# 6502Attempt1.net
KiCad netlist of a schematic drawn in EasyEDA
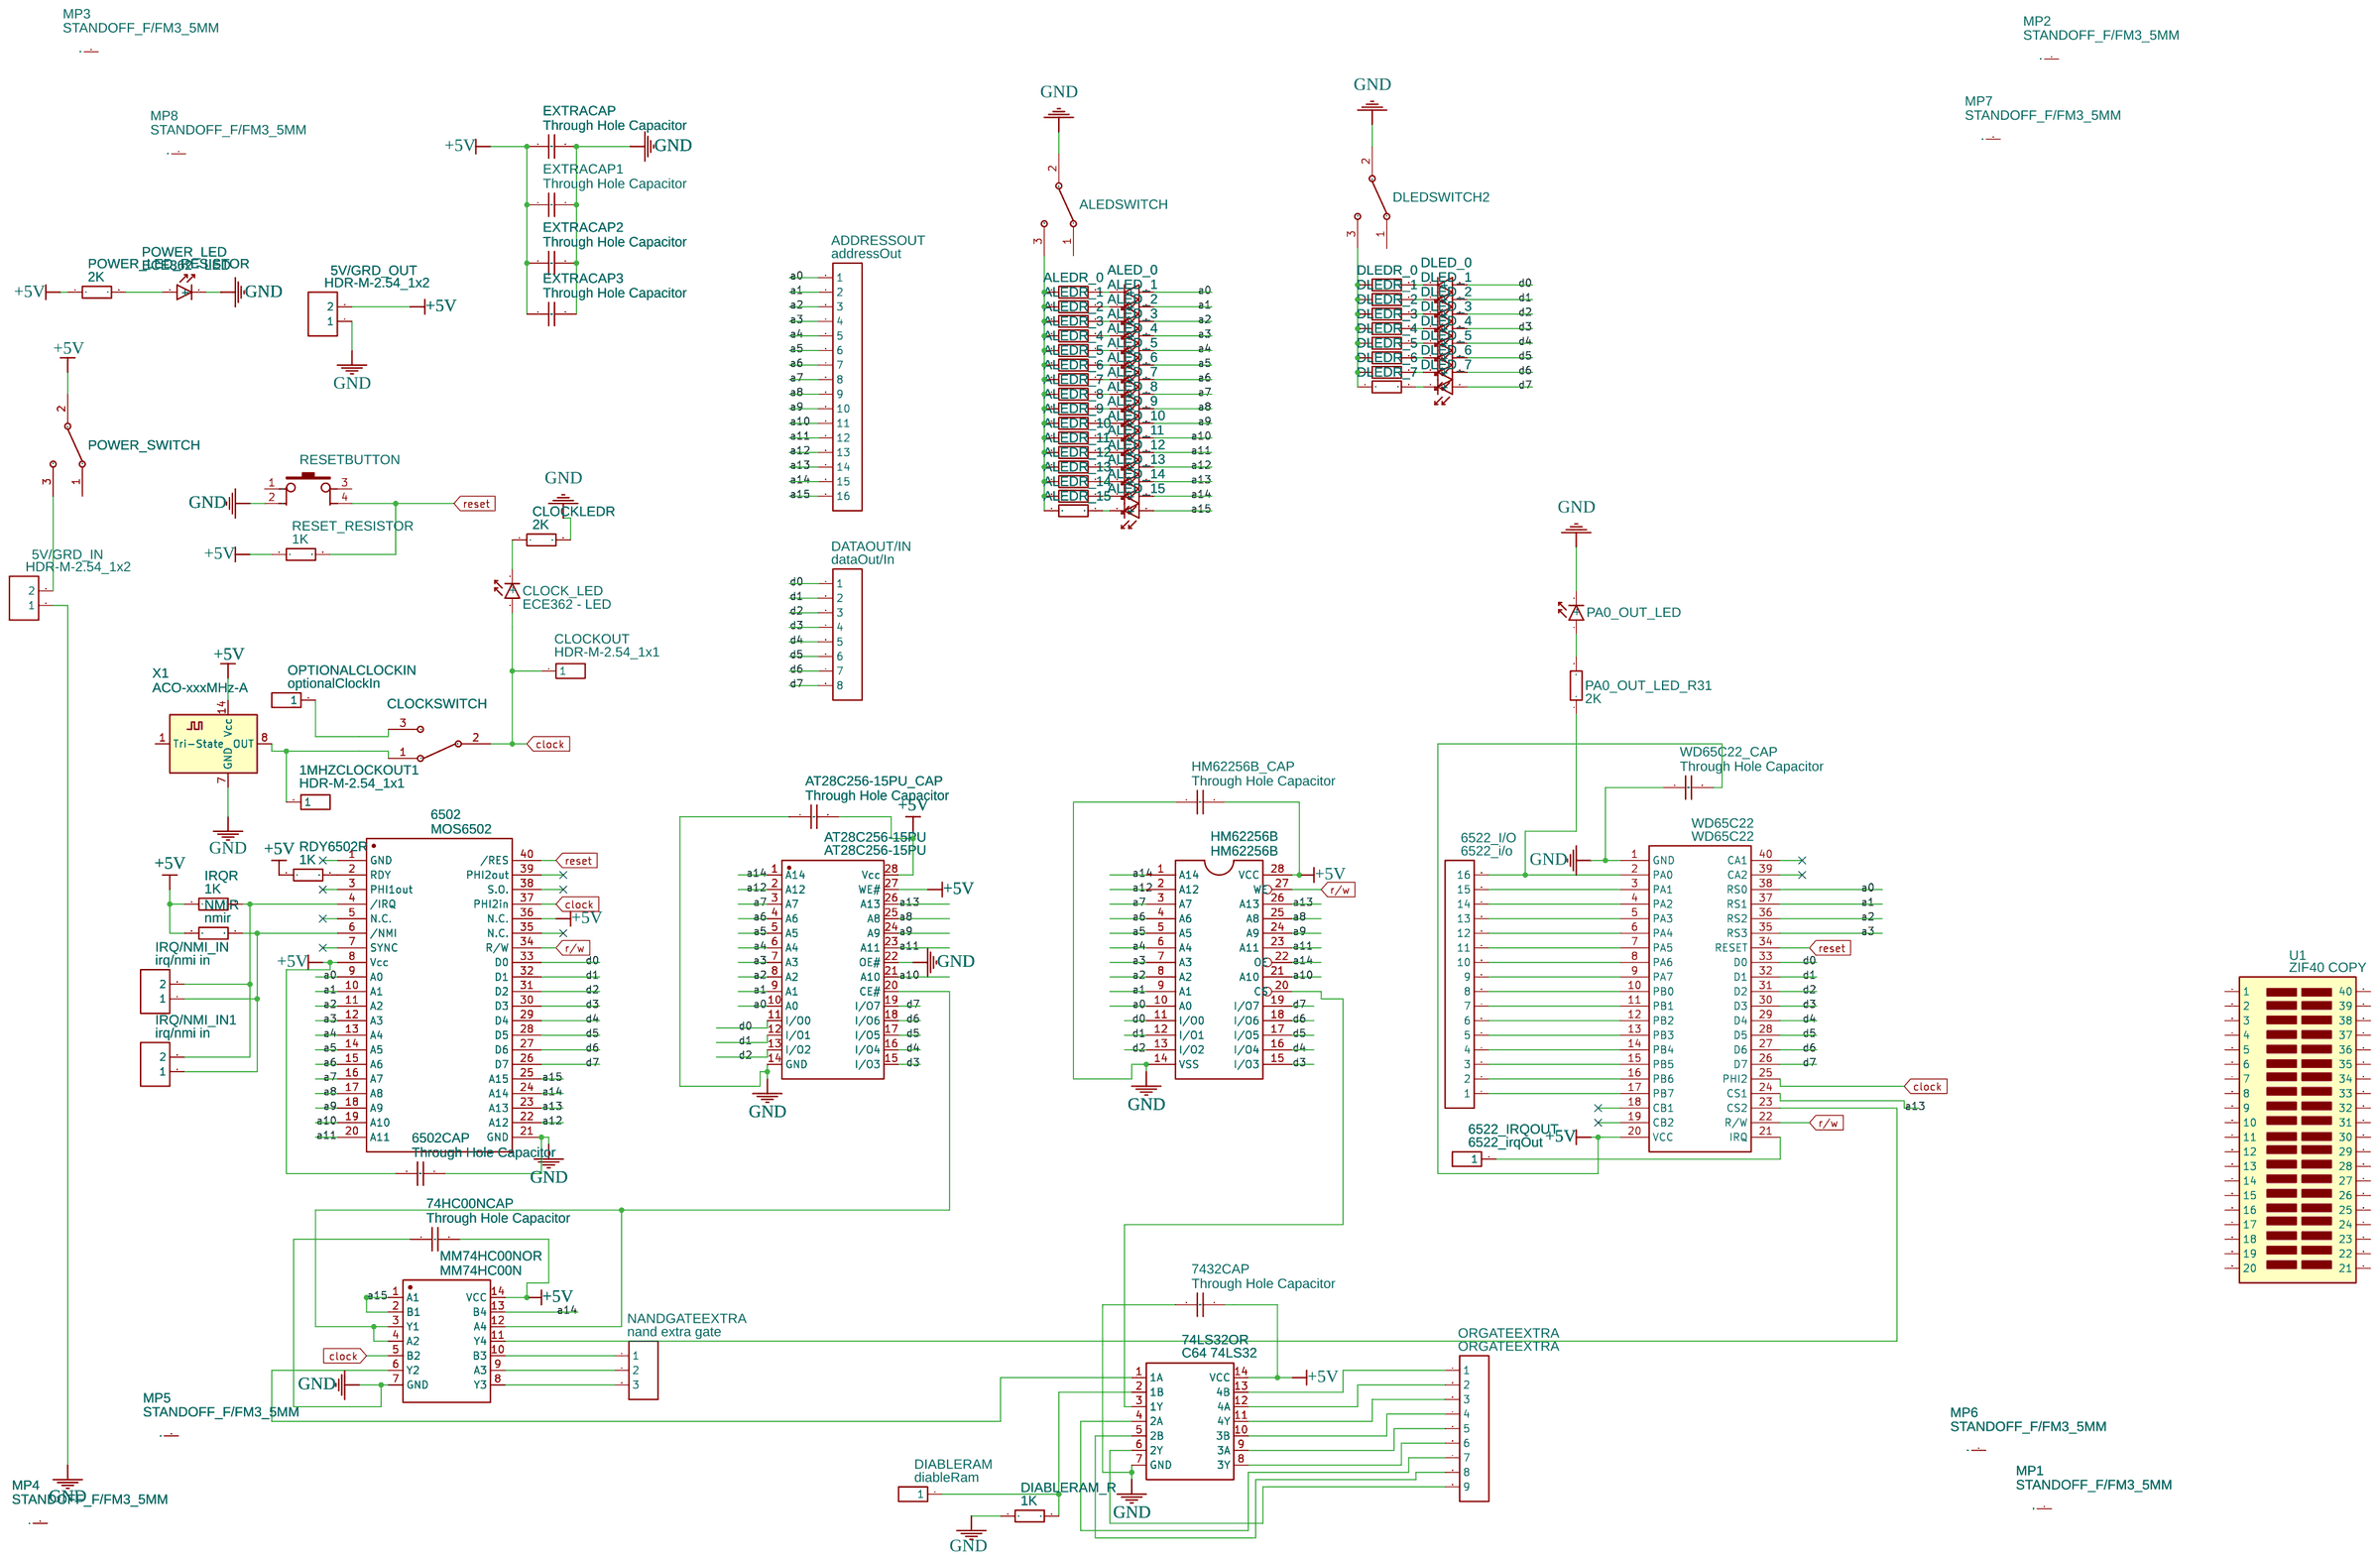
[diagram p0: schematic sheet]

(export (version "E")
  (design (tool "Eeschema 10.0.6"))
  (components
    (comp (ref "1MHZCLOCKOUT1")
      (value "HDR-M-2.54_1x1")
      (fields (field (name "BOM_Supplier Part") "C81276"))
      (libsource (lib "") (part "HDR-M-2.54_1x1"))
    )
    (comp (ref "5V/GRD_IN")
      (value "HDR-M-2.54_1x2")
      (fields (field (name "BOM_Supplier Part") "C124375"))
      (libsource (lib "") (part "HDR-M-2.54_1x2_1"))
    )
    (comp (ref "5V/GRD_OUT")
      (value "HDR-M-2.54_1x2")
      (fields (field (name "BOM_Supplier Part") "C124375"))
      (libsource (lib "") (part "HDR-M-2.54_1x2"))
    )
    (comp (ref "74HC00NCAP")
      (value "Through Hole Capacitor")
      (fields (field (name "BOM_Manufacturer Part") "TAP106K016SCS"))
      (libsource (lib "") (part "Through Hole Capacitor_1"))
    )
    (comp (ref "74LS32OR") (value "C64 74LS32") (libsource (lib "") (part "C64 74LS32")))
    (comp (ref "6502") (value "MOS6502") (libsource (lib "") (part "MOS6502")))
    (comp (ref "6502CAP")
      (value "Through Hole Capacitor")
      (fields (field (name "BOM_Manufacturer Part") "TAP106K016SCS"))
      (libsource (lib "") (part "Through Hole Capacitor_2"))
    )
    (comp (ref "6522_I/O") (value "6522_i/o") (libsource (lib "") (part "HDR-M-2.54_1x16_1")))
    (comp (ref "6522_IRQOUT")
      (value "6522_irqOut")
      (fields (field (name "BOM_Supplier Part") "C81276"))
      (libsource (lib "") (part "HDR-M-2.54_1x1_3"))
    )
    (comp (ref "7432CAP")
      (value "Through Hole Capacitor")
      (fields (field (name "BOM_Manufacturer Part") "TAP106K016SCS"))
      (libsource (lib "") (part "Through Hole Capacitor_3"))
    )
    (comp (ref "ADDRESSOUT") (value "addressOut") (libsource (lib "") (part "HDR-M-2.54_1x16")))
    (comp (ref "ALEDR_0")
      (value "2K")
      (fields
        (field (name "BOM_Manufacturer Part") "EWWR0006J10K0T9")
        (field (name "BOM_Supplier Part") "C348946")
      )
      (libsource (lib "") (part "GENERIC THROUGH HOLE RESISTOR 2"))
    )
    (comp (ref "ALEDR_1")
      (value "2K")
      (fields
        (field (name "BOM_Manufacturer Part") "EWWR0006J10K0T9")
        (field (name "BOM_Supplier Part") "C348946")
      )
      (libsource (lib "") (part "GENERIC THROUGH HOLE RESISTOR 2"))
    )
    (comp (ref "ALEDR_2")
      (value "2K")
      (fields
        (field (name "BOM_Manufacturer Part") "EWWR0006J10K0T9")
        (field (name "BOM_Supplier Part") "C348946")
      )
      (libsource (lib "") (part "GENERIC THROUGH HOLE RESISTOR 2"))
    )
    (comp (ref "ALEDR_3")
      (value "2K")
      (fields
        (field (name "BOM_Manufacturer Part") "EWWR0006J10K0T9")
        (field (name "BOM_Supplier Part") "C348946")
      )
      (libsource (lib "") (part "GENERIC THROUGH HOLE RESISTOR 2"))
    )
    (comp (ref "ALEDR_4")
      (value "2K")
      (fields
        (field (name "BOM_Manufacturer Part") "EWWR0006J10K0T9")
        (field (name "BOM_Supplier Part") "C348946")
      )
      (libsource (lib "") (part "GENERIC THROUGH HOLE RESISTOR 2"))
    )
    (comp (ref "ALEDR_5")
      (value "2K")
      (fields
        (field (name "BOM_Manufacturer Part") "EWWR0006J10K0T9")
        (field (name "BOM_Supplier Part") "C348946")
      )
      (libsource (lib "") (part "GENERIC THROUGH HOLE RESISTOR 2"))
    )
    (comp (ref "ALEDR_6")
      (value "2K")
      (fields
        (field (name "BOM_Manufacturer Part") "EWWR0006J10K0T9")
        (field (name "BOM_Supplier Part") "C348946")
      )
      (libsource (lib "") (part "GENERIC THROUGH HOLE RESISTOR 2"))
    )
    (comp (ref "ALEDR_7")
      (value "2K")
      (fields
        (field (name "BOM_Manufacturer Part") "EWWR0006J10K0T9")
        (field (name "BOM_Supplier Part") "C348946")
      )
      (libsource (lib "") (part "GENERIC THROUGH HOLE RESISTOR 2"))
    )
    (comp (ref "ALEDR_8")
      (value "2K")
      (fields
        (field (name "BOM_Manufacturer Part") "EWWR0006J10K0T9")
        (field (name "BOM_Supplier Part") "C348946")
      )
      (libsource (lib "") (part "GENERIC THROUGH HOLE RESISTOR 2"))
    )
    (comp (ref "ALEDR_9")
      (value "2K")
      (fields
        (field (name "BOM_Manufacturer Part") "EWWR0006J10K0T9")
        (field (name "BOM_Supplier Part") "C348946")
      )
      (libsource (lib "") (part "GENERIC THROUGH HOLE RESISTOR 2"))
    )
    (comp (ref "ALEDR_10")
      (value "2K")
      (fields
        (field (name "BOM_Manufacturer Part") "EWWR0006J10K0T9")
        (field (name "BOM_Supplier Part") "C348946")
      )
      (libsource (lib "") (part "GENERIC THROUGH HOLE RESISTOR 2"))
    )
    (comp (ref "ALEDR_11")
      (value "2K")
      (fields
        (field (name "BOM_Manufacturer Part") "EWWR0006J10K0T9")
        (field (name "BOM_Supplier Part") "C348946")
      )
      (libsource (lib "") (part "GENERIC THROUGH HOLE RESISTOR 2"))
    )
    (comp (ref "ALEDR_12")
      (value "2K")
      (fields
        (field (name "BOM_Manufacturer Part") "EWWR0006J10K0T9")
        (field (name "BOM_Supplier Part") "C348946")
      )
      (libsource (lib "") (part "GENERIC THROUGH HOLE RESISTOR 2"))
    )
    (comp (ref "ALEDR_13")
      (value "2K")
      (fields
        (field (name "BOM_Manufacturer Part") "EWWR0006J10K0T9")
        (field (name "BOM_Supplier Part") "C348946")
      )
      (libsource (lib "") (part "GENERIC THROUGH HOLE RESISTOR 2"))
    )
    (comp (ref "ALEDR_14")
      (value "2K")
      (fields
        (field (name "BOM_Manufacturer Part") "EWWR0006J10K0T9")
        (field (name "BOM_Supplier Part") "C348946")
      )
      (libsource (lib "") (part "GENERIC THROUGH HOLE RESISTOR 2"))
    )
    (comp (ref "ALEDR_15")
      (value "2K")
      (fields
        (field (name "BOM_Manufacturer Part") "EWWR0006J10K0T9")
        (field (name "BOM_Supplier Part") "C348946")
      )
      (libsource (lib "") (part "GENERIC THROUGH HOLE RESISTOR 2"))
    )
    (comp (ref "ALEDSWITCH")
      (value "Slide Switches_SPDT(Single Pole Double Throw)")
      (libsource (lib "") (part "Slide Switches_SPDT(Single Pole Double Throw)_1"))
    )
    (comp (ref "ALED_0") (value "ECE362 - LED") (libsource (lib "") (part "ECE362 - LED")))
    (comp (ref "ALED_1") (value "ECE362 - LED") (libsource (lib "") (part "ECE362 - LED")))
    (comp (ref "ALED_2") (value "ECE362 - LED") (libsource (lib "") (part "ECE362 - LED")))
    (comp (ref "ALED_3") (value "ECE362 - LED") (libsource (lib "") (part "ECE362 - LED")))
    (comp (ref "ALED_4") (value "ECE362 - LED") (libsource (lib "") (part "ECE362 - LED")))
    (comp (ref "ALED_5") (value "ECE362 - LED") (libsource (lib "") (part "ECE362 - LED")))
    (comp (ref "ALED_6") (value "ECE362 - LED") (libsource (lib "") (part "ECE362 - LED")))
    (comp (ref "ALED_7") (value "ECE362 - LED") (libsource (lib "") (part "ECE362 - LED")))
    (comp (ref "ALED_8") (value "ECE362 - LED") (libsource (lib "") (part "ECE362 - LED")))
    (comp (ref "ALED_9") (value "ECE362 - LED") (libsource (lib "") (part "ECE362 - LED")))
    (comp (ref "ALED_10") (value "ECE362 - LED") (libsource (lib "") (part "ECE362 - LED")))
    (comp (ref "ALED_11") (value "ECE362 - LED") (libsource (lib "") (part "ECE362 - LED")))
    (comp (ref "ALED_12") (value "ECE362 - LED") (libsource (lib "") (part "ECE362 - LED")))
    (comp (ref "ALED_13") (value "ECE362 - LED") (libsource (lib "") (part "ECE362 - LED")))
    (comp (ref "ALED_14") (value "ECE362 - LED") (libsource (lib "") (part "ECE362 - LED")))
    (comp (ref "ALED_15") (value "ECE362 - LED") (libsource (lib "") (part "ECE362 - LED")))
    (comp (ref "AT28C256-15PU")
      (value "AT28C256-15PU")
      (fields (field (name "BOM_Supplier Part") "C1348752"))
      (libsource (lib "") (part "AT28C256-15PU"))
    )
    (comp (ref "AT28C256-15PU_CAP")
      (value "Through Hole Capacitor")
      (fields (field (name "BOM_Manufacturer Part") "TAP106K016SCS"))
      (libsource (lib "") (part "Through Hole Capacitor_6"))
    )
    (comp (ref "CLOCKLEDR")
      (value "2K")
      (fields
        (field (name "BOM_Manufacturer Part") "EWWR0006J10K0T9")
        (field (name "BOM_Supplier Part") "C348946")
      )
      (libsource (lib "") (part "GENERIC THROUGH HOLE RESISTOR 2_1"))
    )
    (comp (ref "CLOCKOUT")
      (value "HDR-M-2.54_1x1")
      (fields (field (name "BOM_Supplier Part") "C81276"))
      (libsource (lib "") (part "HDR-M-2.54_1x1_1"))
    )
    (comp (ref "CLOCKSWITCH")
      (value "Slide Switches_SPDT(Single Pole Double Throw)")
      (libsource (lib "") (part "Slide Switches_SPDT(Single Pole Double Throw)_3"))
    )
    (comp (ref "CLOCK_LED") (value "ECE362 - LED") (libsource (lib "") (part "ECE362 - LED_3")))
    (comp (ref "DATAOUT/IN")
      (value "dataOut/In")
      (fields (field (name "BOM_Supplier Part") "C190820"))
      (libsource (lib "") (part "HDR-M-2.54_1x8"))
    )
    (comp (ref "DIABLERAM")
      (value "diableRam")
      (fields (field (name "BOM_Supplier Part") "C81276"))
      (libsource (lib "") (part "HDR-M-2.54_1x1_2"))
    )
    (comp (ref "DIABLERAM_R")
      (value "1K")
      (fields
        (field (name "BOM_Manufacturer Part") "EWWR0006J10K0T9")
        (field (name "BOM_Supplier Part") "C348946")
      )
      (libsource (lib "") (part "GENERIC THROUGH HOLE RESISTOR 2_6"))
    )
    (comp (ref "DLEDR_0")
      (value "2K")
      (fields
        (field (name "BOM_Manufacturer Part") "EWWR0006J10K0T9")
        (field (name "BOM_Supplier Part") "C348946")
      )
      (libsource (lib "") (part "GENERIC THROUGH HOLE RESISTOR 2_2"))
    )
    (comp (ref "DLEDR_1")
      (value "2K")
      (fields
        (field (name "BOM_Manufacturer Part") "EWWR0006J10K0T9")
        (field (name "BOM_Supplier Part") "C348946")
      )
      (libsource (lib "") (part "GENERIC THROUGH HOLE RESISTOR 2_2"))
    )
    (comp (ref "DLEDR_2")
      (value "2K")
      (fields
        (field (name "BOM_Manufacturer Part") "EWWR0006J10K0T9")
        (field (name "BOM_Supplier Part") "C348946")
      )
      (libsource (lib "") (part "GENERIC THROUGH HOLE RESISTOR 2_2"))
    )
    (comp (ref "DLEDR_3")
      (value "2K")
      (fields
        (field (name "BOM_Manufacturer Part") "EWWR0006J10K0T9")
        (field (name "BOM_Supplier Part") "C348946")
      )
      (libsource (lib "") (part "GENERIC THROUGH HOLE RESISTOR 2_2"))
    )
    (comp (ref "DLEDR_4")
      (value "2K")
      (fields
        (field (name "BOM_Manufacturer Part") "EWWR0006J10K0T9")
        (field (name "BOM_Supplier Part") "C348946")
      )
      (libsource (lib "") (part "GENERIC THROUGH HOLE RESISTOR 2_2"))
    )
    (comp (ref "DLEDR_5")
      (value "2K")
      (fields
        (field (name "BOM_Manufacturer Part") "EWWR0006J10K0T9")
        (field (name "BOM_Supplier Part") "C348946")
      )
      (libsource (lib "") (part "GENERIC THROUGH HOLE RESISTOR 2_2"))
    )
    (comp (ref "DLEDR_6")
      (value "2K")
      (fields
        (field (name "BOM_Manufacturer Part") "EWWR0006J10K0T9")
        (field (name "BOM_Supplier Part") "C348946")
      )
      (libsource (lib "") (part "GENERIC THROUGH HOLE RESISTOR 2_2"))
    )
    (comp (ref "DLEDR_7")
      (value "2K")
      (fields
        (field (name "BOM_Manufacturer Part") "EWWR0006J10K0T9")
        (field (name "BOM_Supplier Part") "C348946")
      )
      (libsource (lib "") (part "GENERIC THROUGH HOLE RESISTOR 2_2"))
    )
    (comp (ref "DLEDSWITCH2")
      (value "Slide Switches_SPDT(Single Pole Double Throw)")
      (libsource (lib "") (part "Slide Switches_SPDT(Single Pole Double Throw)"))
    )
    (comp (ref "DLED_0") (value "ECE362 - LED") (libsource (lib "") (part "ECE362 - LED_1")))
    (comp (ref "DLED_1") (value "ECE362 - LED") (libsource (lib "") (part "ECE362 - LED_1")))
    (comp (ref "DLED_2") (value "ECE362 - LED") (libsource (lib "") (part "ECE362 - LED_1")))
    (comp (ref "DLED_3") (value "ECE362 - LED") (libsource (lib "") (part "ECE362 - LED_1")))
    (comp (ref "DLED_4") (value "ECE362 - LED") (libsource (lib "") (part "ECE362 - LED_1")))
    (comp (ref "DLED_5") (value "ECE362 - LED") (libsource (lib "") (part "ECE362 - LED_1")))
    (comp (ref "DLED_6") (value "ECE362 - LED") (libsource (lib "") (part "ECE362 - LED_1")))
    (comp (ref "DLED_7") (value "ECE362 - LED") (libsource (lib "") (part "ECE362 - LED_1")))
    (comp (ref "EXTRACAP")
      (value "Through Hole Capacitor")
      (fields (field (name "BOM_Manufacturer Part") "TAP106K016SCS"))
      (libsource (lib "") (part "Through Hole Capacitor"))
    )
    (comp (ref "EXTRACAP1")
      (value "Through Hole Capacitor")
      (fields (field (name "BOM_Manufacturer Part") "TAP106K016SCS"))
      (libsource (lib "") (part "Through Hole Capacitor"))
    )
    (comp (ref "EXTRACAP2")
      (value "Through Hole Capacitor")
      (fields (field (name "BOM_Manufacturer Part") "TAP106K016SCS"))
      (libsource (lib "") (part "Through Hole Capacitor"))
    )
    (comp (ref "EXTRACAP3")
      (value "Through Hole Capacitor")
      (fields (field (name "BOM_Manufacturer Part") "TAP106K016SCS"))
      (libsource (lib "") (part "Through Hole Capacitor"))
    )
    (comp (ref "HM62256B") (value "HM62256B") (libsource (lib "") (part "HM62256B")))
    (comp (ref "HM62256B_CAP")
      (value "Through Hole Capacitor")
      (fields (field (name "BOM_Manufacturer Part") "TAP106K016SCS"))
      (libsource (lib "") (part "Through Hole Capacitor_5"))
    )
    (comp (ref "IRQ/NMI_IN")
      (value "irq/nmi in")
      (fields (field (name "BOM_Supplier Part") "C49661"))
      (libsource (lib "") (part "HDR-F-2.54_1x2"))
    )
    (comp (ref "IRQ/NMI_IN1")
      (value "irq/nmi in")
      (fields (field (name "BOM_Supplier Part") "C49661"))
      (libsource (lib "") (part "HDR-F-2.54_1x2"))
    )
    (comp (ref "IRQR")
      (value "1K")
      (fields
        (field (name "BOM_Manufacturer Part") "EWWR0006J10K0T9")
        (field (name "BOM_Supplier Part") "C348946")
      )
      (libsource (lib "") (part "GENERIC THROUGH HOLE RESISTOR 2_7"))
    )
    (comp (ref "MM74HC00NOR") (value "MM74HC00N") (libsource (lib "") (part "MM74HC00N")))
    (comp (ref "MP1") (value "STANDOFF_F/FM3_5MM") (libsource (lib "") (part "STANDOFF_F/FM3_5MM")))
    (comp (ref "MP2") (value "STANDOFF_F/FM3_5MM") (libsource (lib "") (part "STANDOFF_F/FM3_5MM")))
    (comp (ref "MP3") (value "STANDOFF_F/FM3_5MM") (libsource (lib "") (part "STANDOFF_F/FM3_5MM")))
    (comp (ref "MP4") (value "STANDOFF_F/FM3_5MM") (libsource (lib "") (part "STANDOFF_F/FM3_5MM")))
    (comp (ref "MP5") (value "STANDOFF_F/FM3_5MM") (libsource (lib "") (part "STANDOFF_F/FM3_5MM")))
    (comp (ref "MP6") (value "STANDOFF_F/FM3_5MM") (libsource (lib "") (part "STANDOFF_F/FM3_5MM")))
    (comp (ref "MP7") (value "STANDOFF_F/FM3_5MM") (libsource (lib "") (part "STANDOFF_F/FM3_5MM")))
    (comp (ref "MP8") (value "STANDOFF_F/FM3_5MM") (libsource (lib "") (part "STANDOFF_F/FM3_5MM")))
    (comp (ref "NANDGATEEXTRA")
      (value "nand extra gate")
      (fields (field (name "BOM_Supplier Part") "C180248"))
      (libsource (lib "") (part "HDR-M-2.54_1x3"))
    )
    (comp (ref "NMIR")
      (value "nmir")
      (fields
        (field (name "BOM_Manufacturer Part") "EWWR0006J10K0T9")
        (field (name "BOM_Supplier Part") "C348946")
      )
      (libsource (lib "") (part "GENERIC THROUGH HOLE RESISTOR 2_3"))
    )
    (comp (ref "OPTIONALCLOCKIN")
      (value "optionalClockIn")
      (fields (field (name "BOM_Supplier Part") "C81276"))
      (libsource (lib "") (part "HDR-M-2.54_1x1_4"))
    )
    (comp (ref "ORGATEEXTRA")
      (value "ORGATEEXTRA")
      (fields (field (name "BOM_Supplier Part") "C225484"))
      (libsource (lib "") (part "HDR-M-2.54_1x9"))
    )
    (comp (ref "PA0_OUT_LED") (value "ECE362 - LED") (libsource (lib "") (part "ECE362 - LED_4")))
    (comp (ref "PA0_OUT_LED_R31")
      (value "2K")
      (fields
        (field (name "BOM_Manufacturer Part") "EWWR0006J10K0T9")
        (field (name "BOM_Supplier Part") "C348946")
      )
      (libsource (lib "") (part "GENERIC THROUGH HOLE RESISTOR 2_5"))
    )
    (comp (ref "POWER_LED") (value "ECE362 - LED") (libsource (lib "") (part "ECE362 - LED_2")))
    (comp (ref "POWER_LED_RESISTOR")
      (value "2K")
      (fields
        (field (name "BOM_Manufacturer Part") "EWWR0006J10K0T9")
        (field (name "BOM_Supplier Part") "C348946")
      )
      (libsource (lib "") (part "GENERIC THROUGH HOLE RESISTOR 2_8"))
    )
    (comp (ref "POWER_SWITCH")
      (value "Slide Switches_SPDT(Single Pole Double Throw)")
      (libsource (lib "") (part "Slide Switches_SPDT(Single Pole Double Throw)_2"))
    )
    (comp (ref "RDY6502R")
      (value "1K")
      (fields
        (field (name "BOM_Manufacturer Part") "EWWR0006J10K0T9")
        (field (name "BOM_Supplier Part") "C348946")
      )
      (libsource (lib "") (part "GENERIC THROUGH HOLE RESISTOR 2_4"))
    )
    (comp (ref "RESETBUTTON")
      (value "PUSHBUTTON 4PIN (4.5MM*6.1MM) COPY")
      (libsource (lib "") (part "PUSHBUTTON 4PIN (4.5MM*6.1MM) COPY"))
    )
    (comp (ref "RESET_RESISTOR")
      (value "1K")
      (fields
        (field (name "BOM_Manufacturer Part") "EWWR0006J10K0T9")
        (field (name "BOM_Supplier Part") "C348946")
      )
      (libsource (lib "") (part "GENERIC THROUGH HOLE RESISTOR 2_9"))
    )
    (comp (ref "U1")
      (value "ZIF40 COPY")
      (fields (field (name "BOM_Manufacturer Part") "New SchematicLib"))
      (libsource (lib "") (part "ZIF40 COPY"))
    )
    (comp (ref "WD65C22") (value "WD65C22") (libsource (lib "") (part "WD65C22")))
    (comp (ref "WD65C22_CAP")
      (value "Through Hole Capacitor")
      (fields (field (name "BOM_Manufacturer Part") "TAP106K016SCS"))
      (libsource (lib "") (part "Through Hole Capacitor_4"))
    )
    (comp (ref "X1") (value "ACO-xxxMHz-A") (libsource (lib "") (part "ACO-xxxMHz-A")))
  )
  (nets
    (net (code "1") (name "+5V") (class "Default")
      (node (ref "5V/GRD_OUT") (pin "2") (pinfunction "2_2") (pintype "unspecified"))
      (node (ref "6502") (pin "36") (pinfunction "N.C._36") (pintype "unspecified"))
      (node (ref "6502") (pin "8") (pinfunction "Vcc_8") (pintype "unspecified"))
      (node (ref "6502CAP") (pin "1") (pinfunction "1_1") (pintype "unspecified"))
      (node (ref "7432CAP") (pin "2") (pinfunction "2_2") (pintype "unspecified"))
      (node (ref "74HC00NCAP") (pin "2") (pinfunction "2_2") (pintype "unspecified"))
      (node (ref "74LS32OR") (pin "14") (pinfunction "VCC_14") (pintype "unspecified"))
      (node (ref "AT28C256-15PU") (pin "27") (pinfunction "WE#_27") (pintype "unspecified"))
      (node (ref "AT28C256-15PU") (pin "28") (pinfunction "Vcc_28") (pintype "unspecified"))
      (node (ref "AT28C256-15PU_CAP") (pin "2") (pinfunction "2_2") (pintype "unspecified"))
      (node (ref "EXTRACAP") (pin "1") (pinfunction "1_1") (pintype "unspecified"))
      (node (ref "EXTRACAP1") (pin "1") (pinfunction "1_1") (pintype "unspecified"))
      (node (ref "EXTRACAP2") (pin "1") (pinfunction "1_1") (pintype "unspecified"))
      (node (ref "EXTRACAP3") (pin "1") (pinfunction "1_1") (pintype "unspecified"))
      (node (ref "HM62256B") (pin "28") (pinfunction "VCC_28") (pintype "unspecified"))
      (node (ref "HM62256B_CAP") (pin "2") (pinfunction "2_2") (pintype "unspecified"))
      (node (ref "IRQR") (pin "1") (pinfunction "1_1") (pintype "unspecified"))
      (node (ref "MM74HC00NOR") (pin "14") (pinfunction "VCC_14") (pintype "unspecified"))
      (node (ref "NMIR") (pin "1") (pinfunction "1_1") (pintype "unspecified"))
      (node (ref "POWER_LED_RESISTOR") (pin "1") (pinfunction "1_1") (pintype "unspecified"))
      (node (ref "POWER_SWITCH") (pin "2") (pinfunction "2_2") (pintype "unspecified"))
      (node (ref "RDY6502R") (pin "1") (pinfunction "1_1") (pintype "unspecified"))
      (node (ref "RESET_RESISTOR") (pin "1") (pinfunction "1_1") (pintype "unspecified"))
      (node (ref "WD65C22") (pin "20") (pinfunction "VCC_20") (pintype "unspecified"))
      (node (ref "WD65C22_CAP") (pin "2") (pinfunction "2_2") (pintype "unspecified"))
      (node (ref "X1") (pin "14") (pinfunction "Vcc_14") (pintype "bidirectional"))
    )
    (net (code "2") (name "/a0") (class "Default")
      (node (ref "6502") (pin "9") (pinfunction "A0_9") (pintype "unspecified"))
      (node (ref "ADDRESSOUT") (pin "1") (pinfunction "1_1") (pintype "unspecified"))
      (node (ref "ALED_0") (pin "1") (pinfunction "+_1") (pintype "unspecified"))
      (node (ref "AT28C256-15PU") (pin "10") (pinfunction "A0_10") (pintype "unspecified"))
      (node (ref "HM62256B") (pin "10") (pinfunction "A0_10") (pintype "unspecified"))
      (node (ref "WD65C22") (pin "38") (pinfunction "RS0_38") (pintype "unspecified"))
    )
    (net (code "3") (name "/a1") (class "Default")
      (node (ref "6502") (pin "10") (pinfunction "A1_10") (pintype "unspecified"))
      (node (ref "ADDRESSOUT") (pin "2") (pinfunction "2_2") (pintype "unspecified"))
      (node (ref "ALED_1") (pin "1") (pinfunction "+_1") (pintype "unspecified"))
      (node (ref "AT28C256-15PU") (pin "9") (pinfunction "A1_9") (pintype "unspecified"))
      (node (ref "HM62256B") (pin "9") (pinfunction "A1_9") (pintype "unspecified"))
      (node (ref "WD65C22") (pin "37") (pinfunction "RS1_37") (pintype "unspecified"))
    )
    (net (code "4") (name "/a2") (class "Default")
      (node (ref "6502") (pin "11") (pinfunction "A2_11") (pintype "unspecified"))
      (node (ref "ADDRESSOUT") (pin "3") (pinfunction "3_3") (pintype "unspecified"))
      (node (ref "ALED_2") (pin "1") (pinfunction "+_1") (pintype "unspecified"))
      (node (ref "AT28C256-15PU") (pin "8") (pinfunction "A2_8") (pintype "unspecified"))
      (node (ref "HM62256B") (pin "8") (pinfunction "A2_8") (pintype "unspecified"))
      (node (ref "WD65C22") (pin "36") (pinfunction "RS2_36") (pintype "unspecified"))
    )
    (net (code "5") (name "/a3") (class "Default")
      (node (ref "6502") (pin "12") (pinfunction "A3_12") (pintype "unspecified"))
      (node (ref "ADDRESSOUT") (pin "4") (pinfunction "4_4") (pintype "unspecified"))
      (node (ref "ALED_3") (pin "1") (pinfunction "+_1") (pintype "unspecified"))
      (node (ref "AT28C256-15PU") (pin "7") (pinfunction "A3_7") (pintype "unspecified"))
      (node (ref "HM62256B") (pin "7") (pinfunction "A3_7") (pintype "unspecified"))
      (node (ref "WD65C22") (pin "35") (pinfunction "RS3_35") (pintype "unspecified"))
    )
    (net (code "6") (name "/a4") (class "Default")
      (node (ref "6502") (pin "13") (pinfunction "A4_13") (pintype "unspecified"))
      (node (ref "ADDRESSOUT") (pin "5") (pinfunction "5_5") (pintype "unspecified"))
      (node (ref "ALED_4") (pin "1") (pinfunction "+_1") (pintype "unspecified"))
      (node (ref "AT28C256-15PU") (pin "6") (pinfunction "A4_6") (pintype "unspecified"))
      (node (ref "HM62256B") (pin "6") (pinfunction "A4_6") (pintype "unspecified"))
    )
    (net (code "7") (name "/a5") (class "Default")
      (node (ref "6502") (pin "14") (pinfunction "A5_14") (pintype "unspecified"))
      (node (ref "ADDRESSOUT") (pin "6") (pinfunction "6_6") (pintype "unspecified"))
      (node (ref "ALED_5") (pin "1") (pinfunction "+_1") (pintype "unspecified"))
      (node (ref "AT28C256-15PU") (pin "5") (pinfunction "A5_5") (pintype "unspecified"))
      (node (ref "HM62256B") (pin "5") (pinfunction "A5_5") (pintype "unspecified"))
    )
    (net (code "8") (name "/a6") (class "Default")
      (node (ref "6502") (pin "15") (pinfunction "A6_15") (pintype "unspecified"))
      (node (ref "ADDRESSOUT") (pin "7") (pinfunction "7_7") (pintype "unspecified"))
      (node (ref "ALED_6") (pin "1") (pinfunction "+_1") (pintype "unspecified"))
      (node (ref "AT28C256-15PU") (pin "4") (pinfunction "A6_4") (pintype "unspecified"))
      (node (ref "HM62256B") (pin "4") (pinfunction "A6_4") (pintype "unspecified"))
    )
    (net (code "9") (name "/a7") (class "Default")
      (node (ref "6502") (pin "16") (pinfunction "A7_16") (pintype "unspecified"))
      (node (ref "ADDRESSOUT") (pin "8") (pinfunction "8_8") (pintype "unspecified"))
      (node (ref "ALED_7") (pin "1") (pinfunction "+_1") (pintype "unspecified"))
      (node (ref "AT28C256-15PU") (pin "3") (pinfunction "A7_3") (pintype "unspecified"))
      (node (ref "HM62256B") (pin "3") (pinfunction "A7_3") (pintype "unspecified"))
    )
    (net (code "10") (name "/a8") (class "Default")
      (node (ref "6502") (pin "17") (pinfunction "A8_17") (pintype "unspecified"))
      (node (ref "ADDRESSOUT") (pin "9") (pinfunction "9_9") (pintype "unspecified"))
      (node (ref "ALED_8") (pin "1") (pinfunction "+_1") (pintype "unspecified"))
      (node (ref "AT28C256-15PU") (pin "25") (pinfunction "A8_25") (pintype "unspecified"))
      (node (ref "HM62256B") (pin "25") (pinfunction "A8_25") (pintype "unspecified"))
    )
    (net (code "11") (name "/a9") (class "Default")
      (node (ref "6502") (pin "18") (pinfunction "A9_18") (pintype "unspecified"))
      (node (ref "ADDRESSOUT") (pin "10") (pinfunction "10_10") (pintype "unspecified"))
      (node (ref "ALED_9") (pin "1") (pinfunction "+_1") (pintype "unspecified"))
      (node (ref "AT28C256-15PU") (pin "24") (pinfunction "A9_24") (pintype "unspecified"))
      (node (ref "HM62256B") (pin "24") (pinfunction "A9_24") (pintype "unspecified"))
    )
    (net (code "12") (name "/a10") (class "Default")
      (node (ref "6502") (pin "19") (pinfunction "A10_19") (pintype "unspecified"))
      (node (ref "ADDRESSOUT") (pin "11") (pinfunction "11_11") (pintype "unspecified"))
      (node (ref "ALED_10") (pin "1") (pinfunction "+_1") (pintype "unspecified"))
      (node (ref "AT28C256-15PU") (pin "21") (pinfunction "A10_21") (pintype "unspecified"))
      (node (ref "HM62256B") (pin "21") (pinfunction "A10_21") (pintype "unspecified"))
    )
    (net (code "13") (name "/a11") (class "Default")
      (node (ref "6502") (pin "20") (pinfunction "A11_20") (pintype "unspecified"))
      (node (ref "ADDRESSOUT") (pin "12") (pinfunction "12_12") (pintype "unspecified"))
      (node (ref "ALED_11") (pin "1") (pinfunction "+_1") (pintype "unspecified"))
      (node (ref "AT28C256-15PU") (pin "23") (pinfunction "A11_23") (pintype "unspecified"))
      (node (ref "HM62256B") (pin "23") (pinfunction "A11_23") (pintype "unspecified"))
    )
    (net (code "14") (name "/a12") (class "Default")
      (node (ref "6502") (pin "22") (pinfunction "A12_22") (pintype "unspecified"))
      (node (ref "ADDRESSOUT") (pin "13") (pinfunction "13_13") (pintype "unspecified"))
      (node (ref "ALED_12") (pin "1") (pinfunction "+_1") (pintype "unspecified"))
      (node (ref "AT28C256-15PU") (pin "2") (pinfunction "A12_2") (pintype "unspecified"))
      (node (ref "HM62256B") (pin "2") (pinfunction "A12_2") (pintype "unspecified"))
    )
    (net (code "15") (name "/a13") (class "Default")
      (node (ref "6502") (pin "23") (pinfunction "A13_23") (pintype "unspecified"))
      (node (ref "ADDRESSOUT") (pin "14") (pinfunction "14_14") (pintype "unspecified"))
      (node (ref "ALED_13") (pin "1") (pinfunction "+_1") (pintype "unspecified"))
      (node (ref "AT28C256-15PU") (pin "26") (pinfunction "A13_26") (pintype "unspecified"))
      (node (ref "HM62256B") (pin "26") (pinfunction "A13_26") (pintype "unspecified"))
      (node (ref "WD65C22") (pin "24") (pinfunction "CS1_24") (pintype "unspecified"))
    )
    (net (code "16") (name "/a14") (class "Default")
      (node (ref "6502") (pin "24") (pinfunction "A14_24") (pintype "unspecified"))
      (node (ref "ADDRESSOUT") (pin "15") (pinfunction "15_15") (pintype "unspecified"))
      (node (ref "ALED_14") (pin "1") (pinfunction "+_1") (pintype "unspecified"))
      (node (ref "AT28C256-15PU") (pin "1") (pinfunction "A14_1") (pintype "unspecified"))
      (node (ref "HM62256B") (pin "1") (pinfunction "A14_1") (pintype "unspecified"))
      (node (ref "HM62256B") (pin "22") (pinfunction "OE_22") (pintype "unspecified"))
      (node (ref "MM74HC00NOR") (pin "13") (pinfunction "B4_13") (pintype "unspecified"))
    )
    (net (code "17") (name "/a15") (class "Default")
      (node (ref "6502") (pin "25") (pinfunction "A15_25") (pintype "unspecified"))
      (node (ref "ADDRESSOUT") (pin "16") (pinfunction "16_16") (pintype "unspecified"))
      (node (ref "ALED_15") (pin "1") (pinfunction "+_1") (pintype "unspecified"))
      (node (ref "MM74HC00NOR") (pin "1") (pinfunction "A1_1") (pintype "unspecified"))
      (node (ref "MM74HC00NOR") (pin "2") (pinfunction "B1_2") (pintype "unspecified"))
    )
    (net (code "18") (name "/d0") (class "Default")
      (node (ref "6502") (pin "33") (pinfunction "D0_33") (pintype "unspecified"))
      (node (ref "AT28C256-15PU") (pin "11") (pinfunction "I/O0_11") (pintype "unspecified"))
      (node (ref "DATAOUT/IN") (pin "1") (pinfunction "1_1") (pintype "unspecified"))
      (node (ref "DLED_0") (pin "1") (pinfunction "+_1") (pintype "unspecified"))
      (node (ref "HM62256B") (pin "11") (pinfunction "I/O0_11") (pintype "unspecified"))
      (node (ref "WD65C22") (pin "33") (pinfunction "D0_33") (pintype "unspecified"))
    )
    (net (code "19") (name "/d1") (class "Default")
      (node (ref "6502") (pin "32") (pinfunction "D1_32") (pintype "unspecified"))
      (node (ref "AT28C256-15PU") (pin "12") (pinfunction "I/O1_12") (pintype "unspecified"))
      (node (ref "DATAOUT/IN") (pin "2") (pinfunction "2_2") (pintype "unspecified"))
      (node (ref "DLED_1") (pin "1") (pinfunction "+_1") (pintype "unspecified"))
      (node (ref "HM62256B") (pin "12") (pinfunction "I/O1_12") (pintype "unspecified"))
      (node (ref "WD65C22") (pin "32") (pinfunction "D1_32") (pintype "unspecified"))
    )
    (net (code "20") (name "/d2") (class "Default")
      (node (ref "6502") (pin "31") (pinfunction "D2_31") (pintype "unspecified"))
      (node (ref "AT28C256-15PU") (pin "13") (pinfunction "I/O2_13") (pintype "unspecified"))
      (node (ref "DATAOUT/IN") (pin "3") (pinfunction "3_3") (pintype "unspecified"))
      (node (ref "DLED_2") (pin "1") (pinfunction "+_1") (pintype "unspecified"))
      (node (ref "HM62256B") (pin "13") (pinfunction "I/O2_13") (pintype "unspecified"))
      (node (ref "WD65C22") (pin "31") (pinfunction "D2_31") (pintype "unspecified"))
    )
    (net (code "21") (name "/d3") (class "Default")
      (node (ref "6502") (pin "30") (pinfunction "D3_30") (pintype "unspecified"))
      (node (ref "AT28C256-15PU") (pin "15") (pinfunction "I/O3_15") (pintype "unspecified"))
      (node (ref "DATAOUT/IN") (pin "4") (pinfunction "4_4") (pintype "unspecified"))
      (node (ref "DLED_3") (pin "1") (pinfunction "+_1") (pintype "unspecified"))
      (node (ref "HM62256B") (pin "15") (pinfunction "I/O3_15") (pintype "unspecified"))
      (node (ref "WD65C22") (pin "30") (pinfunction "D3_30") (pintype "unspecified"))
    )
    (net (code "22") (name "/d4") (class "Default")
      (node (ref "6502") (pin "29") (pinfunction "D4_29") (pintype "unspecified"))
      (node (ref "AT28C256-15PU") (pin "16") (pinfunction "I/O4_16") (pintype "unspecified"))
      (node (ref "DATAOUT/IN") (pin "5") (pinfunction "5_5") (pintype "unspecified"))
      (node (ref "DLED_4") (pin "1") (pinfunction "+_1") (pintype "unspecified"))
      (node (ref "HM62256B") (pin "16") (pinfunction "I/O4_16") (pintype "unspecified"))
      (node (ref "WD65C22") (pin "29") (pinfunction "D4_29") (pintype "unspecified"))
    )
    (net (code "23") (name "/d5") (class "Default")
      (node (ref "6502") (pin "28") (pinfunction "D5_28") (pintype "unspecified"))
      (node (ref "AT28C256-15PU") (pin "17") (pinfunction "I/O5_17") (pintype "unspecified"))
      (node (ref "DATAOUT/IN") (pin "6") (pinfunction "6_6") (pintype "unspecified"))
      (node (ref "DLED_5") (pin "1") (pinfunction "+_1") (pintype "unspecified"))
      (node (ref "HM62256B") (pin "17") (pinfunction "I/O5_17") (pintype "unspecified"))
      (node (ref "WD65C22") (pin "28") (pinfunction "D5_28") (pintype "unspecified"))
    )
    (net (code "24") (name "/d6") (class "Default")
      (node (ref "6502") (pin "27") (pinfunction "D6_27") (pintype "unspecified"))
      (node (ref "AT28C256-15PU") (pin "18") (pinfunction "I/O6_18") (pintype "unspecified"))
      (node (ref "DATAOUT/IN") (pin "7") (pinfunction "7_7") (pintype "unspecified"))
      (node (ref "DLED_6") (pin "1") (pinfunction "+_1") (pintype "unspecified"))
      (node (ref "HM62256B") (pin "18") (pinfunction "I/O6_18") (pintype "unspecified"))
      (node (ref "WD65C22") (pin "27") (pinfunction "D6_27") (pintype "unspecified"))
    )
    (net (code "25") (name "/d7") (class "Default")
      (node (ref "6502") (pin "26") (pinfunction "D7_26") (pintype "unspecified"))
      (node (ref "AT28C256-15PU") (pin "19") (pinfunction "I/O7_19") (pintype "unspecified"))
      (node (ref "DATAOUT/IN") (pin "8") (pinfunction "8_8") (pintype "unspecified"))
      (node (ref "DLED_7") (pin "1") (pinfunction "+_1") (pintype "unspecified"))
      (node (ref "HM62256B") (pin "19") (pinfunction "I/O7_19") (pintype "unspecified"))
      (node (ref "WD65C22") (pin "26") (pinfunction "D7_26") (pintype "unspecified"))
    )
    (net (code "26") (name "GND") (class "Default")
      (node (ref "5V/GRD_IN") (pin "1") (pinfunction "1_1") (pintype "unspecified"))
      (node (ref "5V/GRD_OUT") (pin "1") (pinfunction "1_1") (pintype "unspecified"))
      (node (ref "6502") (pin "21") (pinfunction "GND_21") (pintype "unspecified"))
      (node (ref "6502CAP") (pin "2") (pinfunction "2_2") (pintype "unspecified"))
      (node (ref "7432CAP") (pin "1") (pinfunction "1_1") (pintype "unspecified"))
      (node (ref "74HC00NCAP") (pin "1") (pinfunction "1_1") (pintype "unspecified"))
      (node (ref "74LS32OR") (pin "7") (pinfunction "GND_7") (pintype "unspecified"))
      (node (ref "ALEDSWITCH") (pin "2") (pinfunction "2_2") (pintype "unspecified"))
      (node (ref "AT28C256-15PU") (pin "14") (pinfunction "GND_14") (pintype "unspecified"))
      (node (ref "AT28C256-15PU") (pin "22") (pinfunction "OE#_22") (pintype "unspecified"))
      (node (ref "AT28C256-15PU_CAP") (pin "1") (pinfunction "1_1") (pintype "unspecified"))
      (node (ref "CLOCKLEDR") (pin "2") (pinfunction "2_2") (pintype "unspecified"))
      (node (ref "DIABLERAM_R") (pin "1") (pinfunction "1_1") (pintype "unspecified"))
      (node (ref "DLEDSWITCH2") (pin "2") (pinfunction "2_2") (pintype "unspecified"))
      (node (ref "EXTRACAP") (pin "2") (pinfunction "2_2") (pintype "unspecified"))
      (node (ref "EXTRACAP1") (pin "2") (pinfunction "2_2") (pintype "unspecified"))
      (node (ref "EXTRACAP2") (pin "2") (pinfunction "2_2") (pintype "unspecified"))
      (node (ref "EXTRACAP3") (pin "2") (pinfunction "2_2") (pintype "unspecified"))
      (node (ref "HM62256B") (pin "14") (pinfunction "VSS_14") (pintype "unspecified"))
      (node (ref "HM62256B_CAP") (pin "1") (pinfunction "1_1") (pintype "unspecified"))
      (node (ref "MM74HC00NOR") (pin "7") (pinfunction "GND_7") (pintype "unspecified"))
      (node (ref "PA0_OUT_LED") (pin "2") (pinfunction "-_2") (pintype "unspecified"))
      (node (ref "POWER_LED") (pin "2") (pinfunction "-_2") (pintype "unspecified"))
      (node (ref "RESETBUTTON") (pin "2") (pinfunction "2_2") (pintype "input"))
      (node (ref "WD65C22") (pin "1") (pinfunction "GND_1") (pintype "unspecified"))
      (node (ref "WD65C22_CAP") (pin "1") (pinfunction "1_1") (pintype "unspecified"))
      (node (ref "X1") (pin "7") (pinfunction "GND_7") (pintype "bidirectional"))
    )
    (net (code "27") (name "Net-(5V/GRD_IN-Pad2)") (class "Default")
      (node (ref "5V/GRD_IN") (pin "2") (pinfunction "2_2") (pintype "unspecified"))
      (node (ref "POWER_SWITCH") (pin "3") (pinfunction "3_3") (pintype "unspecified"))
    )
    (net (code "28") (name "Net-(74LS32OR-1A)") (class "Default")
      (node (ref "74LS32OR") (pin "1") (pinfunction "1A_1") (pintype "unspecified"))
      (node (ref "MM74HC00NOR") (pin "6") (pinfunction "Y2_6") (pintype "unspecified"))
    )
    (net (code "29") (name "Net-(74LS32OR-1B)") (class "Default")
      (node (ref "74LS32OR") (pin "2") (pinfunction "1B_2") (pintype "unspecified"))
      (node (ref "DIABLERAM") (pin "1") (pinfunction "1_1") (pintype "input"))
      (node (ref "DIABLERAM_R") (pin "2") (pinfunction "2_2") (pintype "unspecified"))
    )
    (net (code "30") (name "Net-(74LS32OR-1Y)") (class "Default")
      (node (ref "74LS32OR") (pin "3") (pinfunction "1Y_3") (pintype "unspecified"))
      (node (ref "HM62256B") (pin "20") (pinfunction "CS_20") (pintype "unspecified"))
    )
    (net (code "31") (name "Net-(74LS32OR-2A)") (class "Default")
      (node (ref "74LS32OR") (pin "4") (pinfunction "2A_4") (pintype "unspecified"))
      (node (ref "ORGATEEXTRA") (pin "7") (pinfunction "7_7") (pintype "unspecified"))
    )
    (net (code "32") (name "Net-(74LS32OR-2B)") (class "Default")
      (node (ref "74LS32OR") (pin "5") (pinfunction "2B_5") (pintype "unspecified"))
      (node (ref "ORGATEEXTRA") (pin "8") (pinfunction "8_8") (pintype "unspecified"))
    )
    (net (code "33") (name "Net-(74LS32OR-2Y)") (class "Default")
      (node (ref "74LS32OR") (pin "6") (pinfunction "2Y_6") (pintype "unspecified"))
      (node (ref "ORGATEEXTRA") (pin "9") (pinfunction "9_9") (pintype "unspecified"))
    )
    (net (code "34") (name "Net-(74LS32OR-3A)") (class "Default")
      (node (ref "74LS32OR") (pin "9") (pinfunction "3A_9") (pintype "unspecified"))
      (node (ref "ORGATEEXTRA") (pin "5") (pinfunction "5_5") (pintype "unspecified"))
    )
    (net (code "35") (name "Net-(74LS32OR-3B)") (class "Default")
      (node (ref "74LS32OR") (pin "10") (pinfunction "3B_10") (pintype "unspecified"))
      (node (ref "ORGATEEXTRA") (pin "4") (pinfunction "4_4") (pintype "unspecified"))
    )
    (net (code "36") (name "Net-(74LS32OR-3Y)") (class "Default")
      (node (ref "74LS32OR") (pin "8") (pinfunction "3Y_8") (pintype "unspecified"))
      (node (ref "ORGATEEXTRA") (pin "6") (pinfunction "6_6") (pintype "unspecified"))
    )
    (net (code "37") (name "Net-(74LS32OR-4A)") (class "Default")
      (node (ref "74LS32OR") (pin "12") (pinfunction "4A_12") (pintype "unspecified"))
      (node (ref "ORGATEEXTRA") (pin "2") (pinfunction "2_2") (pintype "unspecified"))
    )
    (net (code "38") (name "Net-(74LS32OR-4B)") (class "Default")
      (node (ref "74LS32OR") (pin "13") (pinfunction "4B_13") (pintype "unspecified"))
      (node (ref "ORGATEEXTRA") (pin "1") (pinfunction "1_1") (pintype "unspecified"))
    )
    (net (code "39") (name "Net-(74LS32OR-4Y)") (class "Default")
      (node (ref "74LS32OR") (pin "11") (pinfunction "4Y_11") (pintype "unspecified"))
      (node (ref "ORGATEEXTRA") (pin "3") (pinfunction "3_3") (pintype "unspecified"))
    )
    (net (code "40") (name "Net-(6502-RDY)") (class "Default")
      (node (ref "6502") (pin "2") (pinfunction "RDY_2") (pintype "unspecified"))
      (node (ref "RDY6502R") (pin "2") (pinfunction "2_2") (pintype "unspecified"))
    )
    (net (code "41") (name "Net-(6502-{slash}IRQ)") (class "Default")
      (node (ref "6502") (pin "4") (pinfunction "/IRQ_4") (pintype "unspecified"))
      (node (ref "IRQ/NMI_IN") (pin "2") (pinfunction "2_2") (pintype "input"))
      (node (ref "IRQ/NMI_IN1") (pin "2") (pinfunction "2_2") (pintype "input"))
      (node (ref "IRQR") (pin "2") (pinfunction "2_2") (pintype "unspecified"))
    )
    (net (code "42") (name "Net-(6502-{slash}NMI)") (class "Default")
      (node (ref "6502") (pin "6") (pinfunction "/NMI_6") (pintype "unspecified"))
      (node (ref "IRQ/NMI_IN") (pin "1") (pinfunction "1_1") (pintype "input"))
      (node (ref "IRQ/NMI_IN1") (pin "1") (pinfunction "1_1") (pintype "input"))
      (node (ref "NMIR") (pin "2") (pinfunction "2_2") (pintype "unspecified"))
    )
    (net (code "43") (name "Net-(ALEDR_0-Pad1)") (class "Default")
      (node (ref "ALEDR_0") (pin "1") (pinfunction "1_1") (pintype "unspecified"))
      (node (ref "ALEDR_1") (pin "1") (pinfunction "1_1") (pintype "unspecified"))
      (node (ref "ALEDR_10") (pin "1") (pinfunction "1_1") (pintype "unspecified"))
      (node (ref "ALEDR_11") (pin "1") (pinfunction "1_1") (pintype "unspecified"))
      (node (ref "ALEDR_12") (pin "1") (pinfunction "1_1") (pintype "unspecified"))
      (node (ref "ALEDR_13") (pin "1") (pinfunction "1_1") (pintype "unspecified"))
      (node (ref "ALEDR_14") (pin "1") (pinfunction "1_1") (pintype "unspecified"))
      (node (ref "ALEDR_15") (pin "1") (pinfunction "1_1") (pintype "unspecified"))
      (node (ref "ALEDR_2") (pin "1") (pinfunction "1_1") (pintype "unspecified"))
      (node (ref "ALEDR_3") (pin "1") (pinfunction "1_1") (pintype "unspecified"))
      (node (ref "ALEDR_4") (pin "1") (pinfunction "1_1") (pintype "unspecified"))
      (node (ref "ALEDR_5") (pin "1") (pinfunction "1_1") (pintype "unspecified"))
      (node (ref "ALEDR_6") (pin "1") (pinfunction "1_1") (pintype "unspecified"))
      (node (ref "ALEDR_7") (pin "1") (pinfunction "1_1") (pintype "unspecified"))
      (node (ref "ALEDR_8") (pin "1") (pinfunction "1_1") (pintype "unspecified"))
      (node (ref "ALEDR_9") (pin "1") (pinfunction "1_1") (pintype "unspecified"))
      (node (ref "ALEDSWITCH") (pin "3") (pinfunction "3_3") (pintype "unspecified"))
    )
    (net (code "44") (name "Net-(ALED_0--)") (class "Default")
      (node (ref "ALEDR_0") (pin "2") (pinfunction "2_2") (pintype "unspecified"))
      (node (ref "ALED_0") (pin "2") (pinfunction "-_2") (pintype "unspecified"))
    )
    (net (code "45") (name "Net-(ALED_1--)") (class "Default")
      (node (ref "ALEDR_1") (pin "2") (pinfunction "2_2") (pintype "unspecified"))
      (node (ref "ALED_1") (pin "2") (pinfunction "-_2") (pintype "unspecified"))
    )
    (net (code "46") (name "Net-(ALED_2--)") (class "Default")
      (node (ref "ALEDR_2") (pin "2") (pinfunction "2_2") (pintype "unspecified"))
      (node (ref "ALED_2") (pin "2") (pinfunction "-_2") (pintype "unspecified"))
    )
    (net (code "47") (name "Net-(ALED_3--)") (class "Default")
      (node (ref "ALEDR_3") (pin "2") (pinfunction "2_2") (pintype "unspecified"))
      (node (ref "ALED_3") (pin "2") (pinfunction "-_2") (pintype "unspecified"))
    )
    (net (code "48") (name "Net-(ALED_4--)") (class "Default")
      (node (ref "ALEDR_4") (pin "2") (pinfunction "2_2") (pintype "unspecified"))
      (node (ref "ALED_4") (pin "2") (pinfunction "-_2") (pintype "unspecified"))
    )
    (net (code "49") (name "Net-(ALED_5--)") (class "Default")
      (node (ref "ALEDR_5") (pin "2") (pinfunction "2_2") (pintype "unspecified"))
      (node (ref "ALED_5") (pin "2") (pinfunction "-_2") (pintype "unspecified"))
    )
    (net (code "50") (name "Net-(ALED_6--)") (class "Default")
      (node (ref "ALEDR_6") (pin "2") (pinfunction "2_2") (pintype "unspecified"))
      (node (ref "ALED_6") (pin "2") (pinfunction "-_2") (pintype "unspecified"))
    )
    (net (code "51") (name "Net-(ALED_7--)") (class "Default")
      (node (ref "ALEDR_7") (pin "2") (pinfunction "2_2") (pintype "unspecified"))
      (node (ref "ALED_7") (pin "2") (pinfunction "-_2") (pintype "unspecified"))
    )
    (net (code "52") (name "Net-(ALED_8--)") (class "Default")
      (node (ref "ALEDR_8") (pin "2") (pinfunction "2_2") (pintype "unspecified"))
      (node (ref "ALED_8") (pin "2") (pinfunction "-_2") (pintype "unspecified"))
    )
    (net (code "53") (name "Net-(ALED_9--)") (class "Default")
      (node (ref "ALEDR_9") (pin "2") (pinfunction "2_2") (pintype "unspecified"))
      (node (ref "ALED_9") (pin "2") (pinfunction "-_2") (pintype "unspecified"))
    )
    (net (code "54") (name "Net-(ALED_10--)") (class "Default")
      (node (ref "ALEDR_10") (pin "2") (pinfunction "2_2") (pintype "unspecified"))
      (node (ref "ALED_10") (pin "2") (pinfunction "-_2") (pintype "unspecified"))
    )
    (net (code "55") (name "Net-(ALED_11--)") (class "Default")
      (node (ref "ALEDR_11") (pin "2") (pinfunction "2_2") (pintype "unspecified"))
      (node (ref "ALED_11") (pin "2") (pinfunction "-_2") (pintype "unspecified"))
    )
    (net (code "56") (name "Net-(ALED_12--)") (class "Default")
      (node (ref "ALEDR_12") (pin "2") (pinfunction "2_2") (pintype "unspecified"))
      (node (ref "ALED_12") (pin "2") (pinfunction "-_2") (pintype "unspecified"))
    )
    (net (code "57") (name "Net-(ALED_13--)") (class "Default")
      (node (ref "ALEDR_13") (pin "2") (pinfunction "2_2") (pintype "unspecified"))
      (node (ref "ALED_13") (pin "2") (pinfunction "-_2") (pintype "unspecified"))
    )
    (net (code "58") (name "Net-(ALED_14--)") (class "Default")
      (node (ref "ALEDR_14") (pin "2") (pinfunction "2_2") (pintype "unspecified"))
      (node (ref "ALED_14") (pin "2") (pinfunction "-_2") (pintype "unspecified"))
    )
    (net (code "59") (name "Net-(ALED_15--)") (class "Default")
      (node (ref "ALEDR_15") (pin "2") (pinfunction "2_2") (pintype "unspecified"))
      (node (ref "ALED_15") (pin "2") (pinfunction "-_2") (pintype "unspecified"))
    )
    (net (code "60") (name "Net-(AT28C256-15PU-CE#)") (class "Default")
      (node (ref "AT28C256-15PU") (pin "20") (pinfunction "CE#_20") (pintype "unspecified"))
      (node (ref "MM74HC00NOR") (pin "12") (pinfunction "A4_12") (pintype "unspecified"))
      (node (ref "MM74HC00NOR") (pin "3") (pinfunction "Y1_3") (pintype "unspecified"))
      (node (ref "MM74HC00NOR") (pin "4") (pinfunction "A2_4") (pintype "unspecified"))
    )
    (net (code "61") (name "Net-(CLOCKSWITCH-Pad3)") (class "Default")
      (node (ref "CLOCKSWITCH") (pin "3") (pinfunction "3_3") (pintype "unspecified"))
      (node (ref "OPTIONALCLOCKIN") (pin "1") (pinfunction "1_1") (pintype "input"))
    )
    (net (code "62") (name "Net-(CLOCK_LED--)") (class "Default")
      (node (ref "CLOCKLEDR") (pin "1") (pinfunction "1_1") (pintype "unspecified"))
      (node (ref "CLOCK_LED") (pin "2") (pinfunction "-_2") (pintype "unspecified"))
    )
    (net (code "63") (name "Net-(DLEDR_0-Pad1)") (class "Default")
      (node (ref "DLEDR_0") (pin "1") (pinfunction "1_1") (pintype "unspecified"))
      (node (ref "DLEDR_1") (pin "1") (pinfunction "1_1") (pintype "unspecified"))
      (node (ref "DLEDR_2") (pin "1") (pinfunction "1_1") (pintype "unspecified"))
      (node (ref "DLEDR_3") (pin "1") (pinfunction "1_1") (pintype "unspecified"))
      (node (ref "DLEDR_4") (pin "1") (pinfunction "1_1") (pintype "unspecified"))
      (node (ref "DLEDR_5") (pin "1") (pinfunction "1_1") (pintype "unspecified"))
      (node (ref "DLEDR_6") (pin "1") (pinfunction "1_1") (pintype "unspecified"))
      (node (ref "DLEDR_7") (pin "1") (pinfunction "1_1") (pintype "unspecified"))
      (node (ref "DLEDSWITCH2") (pin "3") (pinfunction "3_3") (pintype "unspecified"))
    )
    (net (code "64") (name "Net-(DLED_0--)") (class "Default")
      (node (ref "DLEDR_0") (pin "2") (pinfunction "2_2") (pintype "unspecified"))
      (node (ref "DLED_0") (pin "2") (pinfunction "-_2") (pintype "unspecified"))
    )
    (net (code "65") (name "Net-(DLED_1--)") (class "Default")
      (node (ref "DLEDR_1") (pin "2") (pinfunction "2_2") (pintype "unspecified"))
      (node (ref "DLED_1") (pin "2") (pinfunction "-_2") (pintype "unspecified"))
    )
    (net (code "66") (name "Net-(DLED_2--)") (class "Default")
      (node (ref "DLEDR_2") (pin "2") (pinfunction "2_2") (pintype "unspecified"))
      (node (ref "DLED_2") (pin "2") (pinfunction "-_2") (pintype "unspecified"))
    )
    (net (code "67") (name "Net-(DLED_3--)") (class "Default")
      (node (ref "DLEDR_3") (pin "2") (pinfunction "2_2") (pintype "unspecified"))
      (node (ref "DLED_3") (pin "2") (pinfunction "-_2") (pintype "unspecified"))
    )
    (net (code "68") (name "Net-(DLED_4--)") (class "Default")
      (node (ref "DLEDR_4") (pin "2") (pinfunction "2_2") (pintype "unspecified"))
      (node (ref "DLED_4") (pin "2") (pinfunction "-_2") (pintype "unspecified"))
    )
    (net (code "69") (name "Net-(DLED_5--)") (class "Default")
      (node (ref "DLEDR_5") (pin "2") (pinfunction "2_2") (pintype "unspecified"))
      (node (ref "DLED_5") (pin "2") (pinfunction "-_2") (pintype "unspecified"))
    )
    (net (code "70") (name "Net-(DLED_6--)") (class "Default")
      (node (ref "DLEDR_6") (pin "2") (pinfunction "2_2") (pintype "unspecified"))
      (node (ref "DLED_6") (pin "2") (pinfunction "-_2") (pintype "unspecified"))
    )
    (net (code "71") (name "Net-(DLED_7--)") (class "Default")
      (node (ref "DLEDR_7") (pin "2") (pinfunction "2_2") (pintype "unspecified"))
      (node (ref "DLED_7") (pin "2") (pinfunction "-_2") (pintype "unspecified"))
    )
    (net (code "72") (name "Net-(MM74HC00NOR-A3)") (class "Default")
      (node (ref "MM74HC00NOR") (pin "9") (pinfunction "A3_9") (pintype "unspecified"))
      (node (ref "NANDGATEEXTRA") (pin "2") (pinfunction "2_2") (pintype "input"))
    )
    (net (code "73") (name "Net-(MM74HC00NOR-B3)") (class "Default")
      (node (ref "MM74HC00NOR") (pin "10") (pinfunction "B3_10") (pintype "unspecified"))
      (node (ref "NANDGATEEXTRA") (pin "1") (pinfunction "1_1") (pintype "input"))
    )
    (net (code "74") (name "Net-(MM74HC00NOR-Y3)") (class "Default")
      (node (ref "MM74HC00NOR") (pin "8") (pinfunction "Y3_8") (pintype "unspecified"))
      (node (ref "NANDGATEEXTRA") (pin "3") (pinfunction "3_3") (pintype "input"))
    )
    (net (code "75") (name "Net-(MM74HC00NOR-Y4)") (class "Default")
      (node (ref "MM74HC00NOR") (pin "11") (pinfunction "Y4_11") (pintype "unspecified"))
      (node (ref "WD65C22") (pin "23") (pinfunction "CS2_23") (pintype "unspecified"))
    )
    (net (code "76") (name "Net-(PA0_OUT_LED-+)") (class "Default")
      (node (ref "PA0_OUT_LED") (pin "1") (pinfunction "+_1") (pintype "unspecified"))
      (node (ref "PA0_OUT_LED_R31") (pin "2") (pinfunction "2_2") (pintype "unspecified"))
    )
    (net (code "77") (name "Net-(POWER_LED-+)") (class "Default")
      (node (ref "POWER_LED") (pin "1") (pinfunction "+_1") (pintype "unspecified"))
      (node (ref "POWER_LED_RESISTOR") (pin "2") (pinfunction "2_2") (pintype "unspecified"))
    )
    (net (code "78") (name "Net-(WD65C22-IRQ)") (class "Default")
      (node (ref "6522_IRQOUT") (pin "1") (pinfunction "1_1") (pintype "input"))
      (node (ref "WD65C22") (pin "21") (pinfunction "IRQ_21") (pintype "unspecified"))
    )
    (net (code "79") (name "Net-(WD65C22-PA0)") (class "Default")
      (node (ref "6522_I/O") (pin "16") (pinfunction "16_16") (pintype "unspecified"))
      (node (ref "PA0_OUT_LED_R31") (pin "1") (pinfunction "1_1") (pintype "unspecified"))
      (node (ref "WD65C22") (pin "2") (pinfunction "PA0_2") (pintype "unspecified"))
    )
    (net (code "80") (name "Net-(WD65C22-PA1)") (class "Default")
      (node (ref "6522_I/O") (pin "15") (pinfunction "15_15") (pintype "unspecified"))
      (node (ref "WD65C22") (pin "3") (pinfunction "PA1_3") (pintype "unspecified"))
    )
    (net (code "81") (name "Net-(WD65C22-PA2)") (class "Default")
      (node (ref "6522_I/O") (pin "14") (pinfunction "14_14") (pintype "unspecified"))
      (node (ref "WD65C22") (pin "4") (pinfunction "PA2_4") (pintype "unspecified"))
    )
    (net (code "82") (name "Net-(WD65C22-PA3)") (class "Default")
      (node (ref "6522_I/O") (pin "13") (pinfunction "13_13") (pintype "unspecified"))
      (node (ref "WD65C22") (pin "5") (pinfunction "PA3_5") (pintype "unspecified"))
    )
    (net (code "83") (name "Net-(WD65C22-PA4)") (class "Default")
      (node (ref "6522_I/O") (pin "12") (pinfunction "12_12") (pintype "unspecified"))
      (node (ref "WD65C22") (pin "6") (pinfunction "PA4_6") (pintype "unspecified"))
    )
    (net (code "84") (name "Net-(WD65C22-PA5)") (class "Default")
      (node (ref "6522_I/O") (pin "11") (pinfunction "11_11") (pintype "unspecified"))
      (node (ref "WD65C22") (pin "7") (pinfunction "PA5_7") (pintype "unspecified"))
    )
    (net (code "85") (name "Net-(WD65C22-PA6)") (class "Default")
      (node (ref "6522_I/O") (pin "10") (pinfunction "10_10") (pintype "unspecified"))
      (node (ref "WD65C22") (pin "8") (pinfunction "PA6_8") (pintype "unspecified"))
    )
    (net (code "86") (name "Net-(WD65C22-PA7)") (class "Default")
      (node (ref "6522_I/O") (pin "9") (pinfunction "9_9") (pintype "unspecified"))
      (node (ref "WD65C22") (pin "9") (pinfunction "PA7_9") (pintype "unspecified"))
    )
    (net (code "87") (name "Net-(WD65C22-PB0)") (class "Default")
      (node (ref "6522_I/O") (pin "8") (pinfunction "8_8") (pintype "unspecified"))
      (node (ref "WD65C22") (pin "10") (pinfunction "PB0_10") (pintype "unspecified"))
    )
    (net (code "88") (name "Net-(WD65C22-PB1)") (class "Default")
      (node (ref "6522_I/O") (pin "7") (pinfunction "7_7") (pintype "unspecified"))
      (node (ref "WD65C22") (pin "11") (pinfunction "PB1_11") (pintype "unspecified"))
    )
    (net (code "89") (name "Net-(WD65C22-PB2)") (class "Default")
      (node (ref "6522_I/O") (pin "6") (pinfunction "6_6") (pintype "unspecified"))
      (node (ref "WD65C22") (pin "12") (pinfunction "PB2_12") (pintype "unspecified"))
    )
    (net (code "90") (name "Net-(WD65C22-PB3)") (class "Default")
      (node (ref "6522_I/O") (pin "5") (pinfunction "5_5") (pintype "unspecified"))
      (node (ref "WD65C22") (pin "13") (pinfunction "PB3_13") (pintype "unspecified"))
    )
    (net (code "91") (name "Net-(WD65C22-PB4)") (class "Default")
      (node (ref "6522_I/O") (pin "4") (pinfunction "4_4") (pintype "unspecified"))
      (node (ref "WD65C22") (pin "14") (pinfunction "PB4_14") (pintype "unspecified"))
    )
    (net (code "92") (name "Net-(WD65C22-PB5)") (class "Default")
      (node (ref "6522_I/O") (pin "3") (pinfunction "3_3") (pintype "unspecified"))
      (node (ref "WD65C22") (pin "15") (pinfunction "PB5_15") (pintype "unspecified"))
    )
    (net (code "93") (name "Net-(WD65C22-PB6)") (class "Default")
      (node (ref "6522_I/O") (pin "2") (pinfunction "2_2") (pintype "unspecified"))
      (node (ref "WD65C22") (pin "16") (pinfunction "PB6_16") (pintype "unspecified"))
    )
    (net (code "94") (name "Net-(WD65C22-PB7)") (class "Default")
      (node (ref "6522_I/O") (pin "1") (pinfunction "1_1") (pintype "unspecified"))
      (node (ref "WD65C22") (pin "17") (pinfunction "PB7_17") (pintype "unspecified"))
    )
    (net (code "95") (name "Net-(X1-OUT)") (class "Default")
      (node (ref "1MHZCLOCKOUT1") (pin "1") (pinfunction "1_1") (pintype "input"))
      (node (ref "CLOCKSWITCH") (pin "1") (pinfunction "1_1") (pintype "unspecified"))
      (node (ref "X1") (pin "8") (pinfunction "OUT_8") (pintype "output"))
    )
    (net (code "96") (name "clock") (class "Default")
      (node (ref "6502") (pin "37") (pinfunction "PHI2in_37") (pintype "unspecified"))
      (node (ref "CLOCKOUT") (pin "1") (pinfunction "1_1") (pintype "input"))
      (node (ref "CLOCKSWITCH") (pin "2") (pinfunction "2_2") (pintype "unspecified"))
      (node (ref "CLOCK_LED") (pin "1") (pinfunction "+_1") (pintype "unspecified"))
      (node (ref "MM74HC00NOR") (pin "5") (pinfunction "B2_5") (pintype "unspecified"))
      (node (ref "WD65C22") (pin "25") (pinfunction "PHI2_25") (pintype "unspecified"))
    )
    (net (code "97") (name "reset") (class "Default")
      (node (ref "6502") (pin "40") (pinfunction "/RES_40") (pintype "unspecified"))
      (node (ref "RESETBUTTON") (pin "4") (pinfunction "4_4") (pintype "input"))
      (node (ref "RESET_RESISTOR") (pin "2") (pinfunction "2_2") (pintype "unspecified"))
      (node (ref "WD65C22") (pin "34") (pinfunction "RESET_34") (pintype "unspecified"))
    )
    (net (code "98") (name "r{slash}w") (class "Default")
      (node (ref "6502") (pin "34") (pinfunction "R/W_34") (pintype "unspecified"))
      (node (ref "HM62256B") (pin "27") (pinfunction "WE_27") (pintype "unspecified"))
      (node (ref "WD65C22") (pin "22") (pinfunction "R/W_22") (pintype "unspecified"))
    )
    (net (code "99") (name "unconnected-(6502-GND-Pad1)") (class "Default")
      (node (ref "6502") (pin "1") (pinfunction "GND_1") (pintype "unspecified+no_connect"))
    )
    (net (code "100") (name "unconnected-(6502-N.C.-Pad5)") (class "Default")
      (node (ref "6502") (pin "5") (pinfunction "N.C._5") (pintype "unspecified+no_connect"))
    )
    (net (code "101") (name "unconnected-(6502-N.C.-Pad35)") (class "Default")
      (node (ref "6502") (pin "35") (pinfunction "N.C._35") (pintype "unspecified+no_connect"))
    )
    (net (code "102") (name "unconnected-(6502-PHI1out-Pad3)") (class "Default")
      (node (ref "6502") (pin "3") (pinfunction "PHI1out_3") (pintype "unspecified+no_connect"))
    )
    (net (code "103") (name "unconnected-(6502-PHI2out-Pad39)") (class "Default")
      (node (ref "6502") (pin "39") (pinfunction "PHI2out_39") (pintype "unspecified+no_connect"))
    )
    (net (code "104") (name "unconnected-(6502-S.O.-Pad38)") (class "Default")
      (node (ref "6502") (pin "38") (pinfunction "S.O._38") (pintype "unspecified+no_connect"))
    )
    (net (code "105") (name "unconnected-(6502-SYNC-Pad7)") (class "Default")
      (node (ref "6502") (pin "7") (pinfunction "SYNC_7") (pintype "unspecified+no_connect"))
    )
    (net (code "106") (name "unconnected-(ALEDSWITCH-Pad1)") (class "Default")
      (node (ref "ALEDSWITCH") (pin "1") (pinfunction "1_1") (pintype "unspecified"))
    )
    (net (code "107") (name "unconnected-(DLEDSWITCH2-Pad1)") (class "Default")
      (node (ref "DLEDSWITCH2") (pin "1") (pinfunction "1_1") (pintype "unspecified"))
    )
    (net (code "108") (name "unconnected-(MP1-P$1-Pad1)") (class "Default")
      (node (ref "MP1") (pin "1") (pinfunction "P$1_1") (pintype "bidirectional"))
    )
    (net (code "109") (name "unconnected-(MP2-P$1-Pad1)") (class "Default")
      (node (ref "MP2") (pin "1") (pinfunction "P$1_1") (pintype "bidirectional"))
    )
    (net (code "110") (name "unconnected-(MP3-P$1-Pad1)") (class "Default")
      (node (ref "MP3") (pin "1") (pinfunction "P$1_1") (pintype "bidirectional"))
    )
    (net (code "111") (name "unconnected-(MP4-P$1-Pad1)") (class "Default")
      (node (ref "MP4") (pin "1") (pinfunction "P$1_1") (pintype "bidirectional"))
    )
    (net (code "112") (name "unconnected-(MP5-P$1-Pad1)") (class "Default")
      (node (ref "MP5") (pin "1") (pinfunction "P$1_1") (pintype "bidirectional"))
    )
    (net (code "113") (name "unconnected-(MP6-P$1-Pad1)") (class "Default")
      (node (ref "MP6") (pin "1") (pinfunction "P$1_1") (pintype "bidirectional"))
    )
    (net (code "114") (name "unconnected-(MP7-P$1-Pad1)") (class "Default")
      (node (ref "MP7") (pin "1") (pinfunction "P$1_1") (pintype "bidirectional"))
    )
    (net (code "115") (name "unconnected-(MP8-P$1-Pad1)") (class "Default")
      (node (ref "MP8") (pin "1") (pinfunction "P$1_1") (pintype "bidirectional"))
    )
    (net (code "116") (name "unconnected-(POWER_SWITCH-Pad1)") (class "Default")
      (node (ref "POWER_SWITCH") (pin "1") (pinfunction "1_1") (pintype "unspecified"))
    )
    (net (code "117") (name "unconnected-(RESETBUTTON-Pad1)") (class "Default")
      (node (ref "RESETBUTTON") (pin "1") (pinfunction "1_1") (pintype "input"))
    )
    (net (code "118") (name "unconnected-(RESETBUTTON-Pad3)") (class "Default")
      (node (ref "RESETBUTTON") (pin "3") (pinfunction "3_3") (pintype "input"))
    )
    (net (code "119") (name "unconnected-(U1-Pad1)") (class "Default")
      (node (ref "U1") (pin "1") (pinfunction "1_1") (pintype "unspecified"))
    )
    (net (code "120") (name "unconnected-(U1-Pad2)") (class "Default")
      (node (ref "U1") (pin "2") (pinfunction "2_2") (pintype "unspecified"))
    )
    (net (code "121") (name "unconnected-(U1-Pad3)") (class "Default")
      (node (ref "U1") (pin "3") (pinfunction "3_3") (pintype "unspecified"))
    )
    (net (code "122") (name "unconnected-(U1-Pad4)") (class "Default")
      (node (ref "U1") (pin "4") (pinfunction "4_4") (pintype "unspecified"))
    )
    (net (code "123") (name "unconnected-(U1-Pad5)") (class "Default")
      (node (ref "U1") (pin "5") (pinfunction "5_5") (pintype "unspecified"))
    )
    (net (code "124") (name "unconnected-(U1-Pad6)") (class "Default")
      (node (ref "U1") (pin "6") (pinfunction "6_6") (pintype "unspecified"))
    )
    (net (code "125") (name "unconnected-(U1-Pad7)") (class "Default")
      (node (ref "U1") (pin "7") (pinfunction "7_7") (pintype "unspecified"))
    )
    (net (code "126") (name "unconnected-(U1-Pad8)") (class "Default")
      (node (ref "U1") (pin "8") (pinfunction "8_8") (pintype "unspecified"))
    )
    (net (code "127") (name "unconnected-(U1-Pad9)") (class "Default")
      (node (ref "U1") (pin "9") (pinfunction "9_9") (pintype "unspecified"))
    )
    (net (code "128") (name "unconnected-(U1-Pad10)") (class "Default")
      (node (ref "U1") (pin "10") (pinfunction "10_10") (pintype "unspecified"))
    )
    (net (code "129") (name "unconnected-(U1-Pad11)") (class "Default")
      (node (ref "U1") (pin "11") (pinfunction "11_11") (pintype "unspecified"))
    )
    (net (code "130") (name "unconnected-(U1-Pad12)") (class "Default")
      (node (ref "U1") (pin "12") (pinfunction "12_12") (pintype "unspecified"))
    )
    (net (code "131") (name "unconnected-(U1-Pad13)") (class "Default")
      (node (ref "U1") (pin "13") (pinfunction "13_13") (pintype "unspecified"))
    )
    (net (code "132") (name "unconnected-(U1-Pad14)") (class "Default")
      (node (ref "U1") (pin "14") (pinfunction "14_14") (pintype "unspecified"))
    )
    (net (code "133") (name "unconnected-(U1-Pad15)") (class "Default")
      (node (ref "U1") (pin "15") (pinfunction "15_15") (pintype "unspecified"))
    )
    (net (code "134") (name "unconnected-(U1-Pad16)") (class "Default")
      (node (ref "U1") (pin "16") (pinfunction "16_16") (pintype "unspecified"))
    )
    (net (code "135") (name "unconnected-(U1-Pad17)") (class "Default")
      (node (ref "U1") (pin "17") (pinfunction "17_17") (pintype "unspecified"))
    )
    (net (code "136") (name "unconnected-(U1-Pad18)") (class "Default")
      (node (ref "U1") (pin "18") (pinfunction "18_18") (pintype "unspecified"))
    )
    (net (code "137") (name "unconnected-(U1-Pad19)") (class "Default")
      (node (ref "U1") (pin "19") (pinfunction "19_19") (pintype "unspecified"))
    )
    (net (code "138") (name "unconnected-(U1-Pad20)") (class "Default")
      (node (ref "U1") (pin "20") (pinfunction "20_20") (pintype "unspecified"))
    )
    (net (code "139") (name "unconnected-(U1-Pad21)") (class "Default")
      (node (ref "U1") (pin "21") (pinfunction "21_21") (pintype "unspecified"))
    )
    (net (code "140") (name "unconnected-(U1-Pad22)") (class "Default")
      (node (ref "U1") (pin "22") (pinfunction "22_22") (pintype "unspecified"))
    )
    (net (code "141") (name "unconnected-(U1-Pad23)") (class "Default")
      (node (ref "U1") (pin "23") (pinfunction "23_23") (pintype "unspecified"))
    )
    (net (code "142") (name "unconnected-(U1-Pad24)") (class "Default")
      (node (ref "U1") (pin "24") (pinfunction "24_24") (pintype "unspecified"))
    )
    (net (code "143") (name "unconnected-(U1-Pad25)") (class "Default")
      (node (ref "U1") (pin "25") (pinfunction "25_25") (pintype "unspecified"))
    )
    (net (code "144") (name "unconnected-(U1-Pad26)") (class "Default")
      (node (ref "U1") (pin "26") (pinfunction "26_26") (pintype "unspecified"))
    )
    (net (code "145") (name "unconnected-(U1-Pad27)") (class "Default")
      (node (ref "U1") (pin "27") (pinfunction "27_27") (pintype "unspecified"))
    )
    (net (code "146") (name "unconnected-(U1-Pad28)") (class "Default")
      (node (ref "U1") (pin "28") (pinfunction "28_28") (pintype "unspecified"))
    )
    (net (code "147") (name "unconnected-(U1-Pad29)") (class "Default")
      (node (ref "U1") (pin "29") (pinfunction "29_29") (pintype "unspecified"))
    )
    (net (code "148") (name "unconnected-(U1-Pad30)") (class "Default")
      (node (ref "U1") (pin "30") (pinfunction "30_30") (pintype "unspecified"))
    )
    (net (code "149") (name "unconnected-(U1-Pad31)") (class "Default")
      (node (ref "U1") (pin "31") (pinfunction "31_31") (pintype "unspecified"))
    )
    (net (code "150") (name "unconnected-(U1-Pad32)") (class "Default")
      (node (ref "U1") (pin "32") (pinfunction "32_32") (pintype "unspecified"))
    )
    (net (code "151") (name "unconnected-(U1-Pad33)") (class "Default")
      (node (ref "U1") (pin "33") (pinfunction "33_33") (pintype "unspecified"))
    )
    (net (code "152") (name "unconnected-(U1-Pad34)") (class "Default")
      (node (ref "U1") (pin "34") (pinfunction "34_34") (pintype "unspecified"))
    )
    (net (code "153") (name "unconnected-(U1-Pad35)") (class "Default")
      (node (ref "U1") (pin "35") (pinfunction "35_35") (pintype "unspecified"))
    )
    (net (code "154") (name "unconnected-(U1-Pad36)") (class "Default")
      (node (ref "U1") (pin "36") (pinfunction "36_36") (pintype "unspecified"))
    )
    (net (code "155") (name "unconnected-(U1-Pad37)") (class "Default")
      (node (ref "U1") (pin "37") (pinfunction "37_37") (pintype "unspecified"))
    )
    (net (code "156") (name "unconnected-(U1-Pad38)") (class "Default")
      (node (ref "U1") (pin "38") (pinfunction "38_38") (pintype "unspecified"))
    )
    (net (code "157") (name "unconnected-(U1-Pad39)") (class "Default")
      (node (ref "U1") (pin "39") (pinfunction "39_39") (pintype "unspecified"))
    )
    (net (code "158") (name "unconnected-(U1-Pad40)") (class "Default")
      (node (ref "U1") (pin "40") (pinfunction "40_40") (pintype "unspecified"))
    )
    (net (code "159") (name "unconnected-(WD65C22-CA1-Pad40)") (class "Default")
      (node (ref "WD65C22") (pin "40") (pinfunction "CA1_40") (pintype "unspecified+no_connect"))
    )
    (net (code "160") (name "unconnected-(WD65C22-CA2-Pad39)") (class "Default")
      (node (ref "WD65C22") (pin "39") (pinfunction "CA2_39") (pintype "unspecified+no_connect"))
    )
    (net (code "161") (name "unconnected-(WD65C22-CB1-Pad18)") (class "Default")
      (node (ref "WD65C22") (pin "18") (pinfunction "CB1_18") (pintype "unspecified+no_connect"))
    )
    (net (code "162") (name "unconnected-(WD65C22-CB2-Pad19)") (class "Default")
      (node (ref "WD65C22") (pin "19") (pinfunction "CB2_19") (pintype "unspecified+no_connect"))
    )
    (net (code "163") (name "unconnected-(X1-Tri-State-Pad1)") (class "Default")
      (node (ref "X1") (pin "1") (pinfunction "Tri-State_1") (pintype "bidirectional"))
    )
  )
)
